# H11R0_Backend.net
KiCad netlist of a schematic drawn in Altium Designer
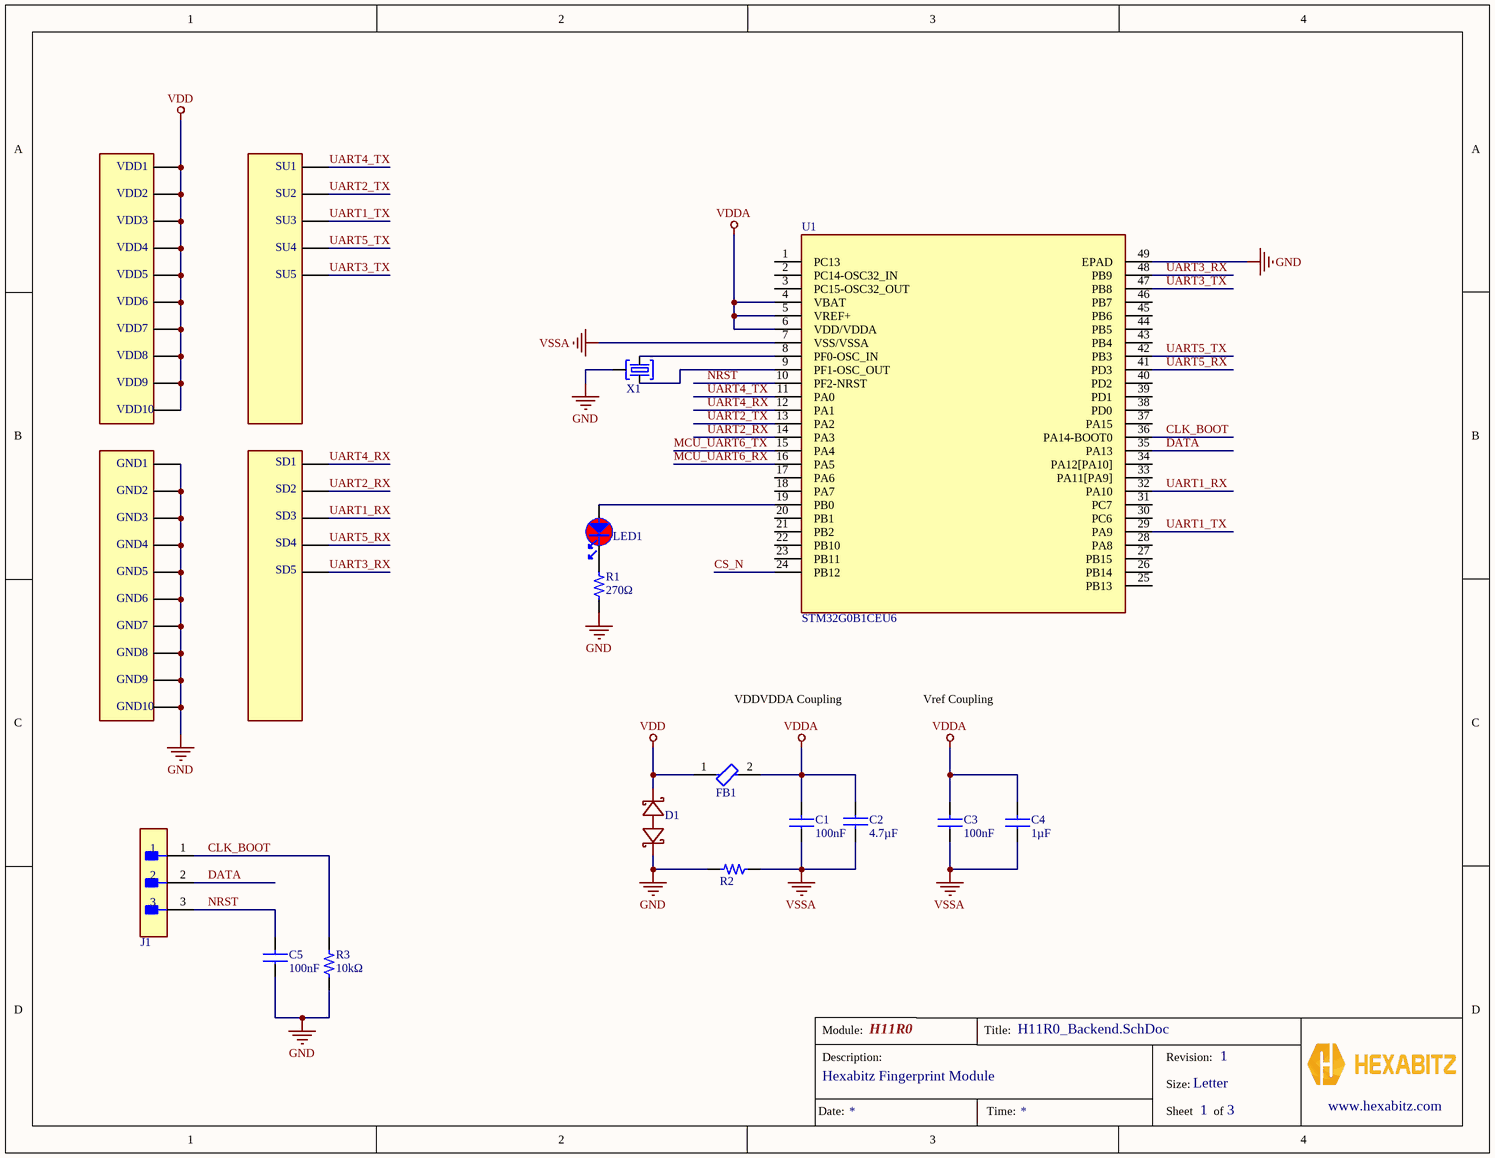
[diagram p0: H11R0_Backend.SchDoc]

(export (version "E")
  (design (tool "Eeschema 10.0.6"))
  (components
    (comp (ref "C1")
      (value "100nF")
      (footprint "C0603")
      (fields
        (field (name "MANUFACTURER") "Samsung Electro-Mechanics")
        (field (name "MANUFACTURER PART NUMBER") "CL10B104KA8NNNC")
        (field (name "TOLERANCE") "10%")
      )
      (libsource (lib "Hexabitz Altium Library") (part "generic Capacitor"))
    )
    (comp (ref "C2")
      (value "4.7µF")
      (footprint "C0805")
      (fields
        (field (name "MANUFACTURER") "Samsung Electro-Mechanics")
        (field (name "MANUFACTURER PART NUMBER") "CL21X475KAQNNNE")
        (field (name "TOLERANCE") "10%")
      )
      (libsource (lib "Hexabitz Altium Library") (part "generic Capacitor"))
    )
    (comp (ref "C3")
      (value "100nF")
      (footprint "C0603")
      (fields
        (field (name "MANUFACTURER") "Samsung Electro-Mechanics")
        (field (name "MANUFACTURER PART NUMBER") "CL10B104KA8NNNC")
        (field (name "TOLERANCE") "10%")
      )
      (libsource (lib "Hexabitz Altium Library") (part "generic Capacitor"))
    )
    (comp (ref "C4")
      (value "1µF")
      (footprint "C0805")
      (description "Ceramic Capacitor, Ceramic, 16V, 10% +Tol, 10% -Tol, X7R, 15% TC, 1uF, Surface Mount, 0805")
      (fields
        (field (name "MANUFACTURER") "Yageo Group")
        (field (name "MANUFACTURER PART NUMBER") "CC0805KKX7R7BB105")
      )
      (libsource (lib "Hexabitz Altium Library") (part "generic Capacitor"))
    )
    (comp (ref "C5")
      (value "100nF")
      (footprint "C0603")
      (fields
        (field (name "MANUFACTURER") "Samsung Electro-Mechanics")
        (field (name "MANUFACTURER PART NUMBER") "CL10B104KA8NNNC")
        (field (name "TOLERANCE") "10%")
      )
      (libsource (lib "Hexabitz Altium Library") (part "generic Capacitor"))
    )
    (comp (ref "D1")
      (value "CDSOD323-T03SC")
      (footprint "SOD2513X114N")
      (description "A 3V, 350W, bi-directional, standard capacitance, SOD323 pkg TVS Diode ¦ Bourns CDSOD323-T03SC")
      (fields (field (name "MANUFACTURER") "Bourns"))
      (libsource (lib "Hexabitz Altium Library") (part "CDSOD323-T03SC"))
    )
    (comp (ref "FB1")
      (value "MMZ1608Y300B")
      (footprint "FP-MMZ1608-0_8-MFG")
      (description "Ferrite Beads 0603 30ohms 1500mA Signal Line AEC-Q200")
      (fields
        (field (name "MANUFACTURER") "TDK")
        (field (name "MANUFACTURER PART NUMBER") "MMZ1608Y300BTD25")
      )
      (libsource (lib "Hexabitz Altium Library") (part "MMZ1608Y300B"))
    )
    (comp (ref "GND1")
      (value "HEXABIT_UART_PORT")
      (footprint "HEXABIT_POWER_PORT_D")
      (libsource (lib "hexabitz_connectors.Library") (part "HEXABIT_POWER_PORT_D"))
    )
    (comp (ref "GND2")
      (value "HEXABIT_UART_PORT")
      (footprint "HEXABIT_POWER_PORT_D")
      (libsource (lib "hexabitz_connectors.Library") (part "HEXABIT_POWER_PORT_D"))
    )
    (comp (ref "GND3")
      (value "HEXABIT_UART_PORT")
      (footprint "HEXABIT_POWER_PORT_D_300R")
      (libsource (lib "hexabitz_connectors.Library") (part "HEXABIT_POWER_PORT_D_300R"))
    )
    (comp (ref "GND4")
      (value "HEXABIT_UART_PORT")
      (footprint "HEXABIT_POWER_PORT_D")
      (libsource (lib "hexabitz_connectors.Library") (part "HEXABIT_POWER_PORT_D"))
    )
    (comp (ref "GND5")
      (value "HEXABIT_UART_PORT")
      (footprint "HEXABIT_POWER_PORT_D")
      (libsource (lib "hexabitz_connectors.Library") (part "HEXABIT_POWER_PORT_D"))
    )
    (comp (ref "GND6")
      (value "HEXABIT_UART_PORT")
      (footprint "HEXABIT_POWER_PORT_D")
      (libsource (lib "hexabitz_connectors.Library") (part "HEXABIT_POWER_PORT_D"))
    )
    (comp (ref "GND7")
      (value "HEXABIT_UART_PORT")
      (footprint "HEXABIT_POWER_PORT_D")
      (libsource (lib "hexabitz_connectors.Library") (part "HEXABIT_POWER_PORT_D"))
    )
    (comp (ref "GND8")
      (value "HEXABIT_UART_PORT")
      (footprint "HEXABIT_POWER_PORT_D_300L")
      (libsource (lib "hexabitz_connectors.Library") (part "HEXABIT_POWER_PORT_D_300L"))
    )
    (comp (ref "GND9")
      (value "HEXABIT_UART_PORT")
      (footprint "HEXABIT_POWER_PORT_D")
      (libsource (lib "hexabitz_connectors.Library") (part "HEXABIT_POWER_PORT_D"))
    )
    (comp (ref "GND10")
      (value "HEXABIT_UART_PORT")
      (footprint "HEXABIT_POWER_PORT_D")
      (libsource (lib "hexabitz_connectors.Library") (part "HEXABIT_POWER_PORT_D"))
    )
    (comp (ref "J1")
      (value "TSW-103-14-G-S")
      (footprint "FP-TSW-103-14-G-S-MFG")
      (description "CONN HEADER VERT 3POS 2.54MM")
      (libsource (lib "Altium Content Vault") (part "cd3439d6ef35ae5d9b27ec4fdd3e828"))
    )
    (comp (ref "LED1")
      (value "VLMS1300-GS08")
      (footprint "FP-6_541-5092_01-4-MFG")
      (description "LED Uni-Color Super Red 639nm 2-Pin Chip 0603(1608Metric) T/R")
      (fields (field (name "MANUFACTURER") "Vishay Semiconductors"))
      (libsource (lib "Hexabitz Altium Library") (part "VLMS1300-GS08"))
    )
    (comp (ref "R1")
      (value "270Ω")
      (footprint "R0603")
      (description "Res Thick Film 0603 270 Ohm 5% 0.1W(1/10W) ±200ppm/C Pad SMD Automotive T/R")
      (fields
        (field (name "MANUFACTURER") "Panasonic")
        (field (name "MANUFACTURER PART NUMBER") "ERJ-3GEYJ271V")
      )
      (libsource (lib "") (part "generic Resistor_2"))
    )
    (comp (ref "R2")
      (value "Manufacturer Part Number")
      (footprint "R0603")
      (libsource (lib "Hexabitz Altium Library") (part "generic Resistor"))
    )
    (comp (ref "R3")
      (value "10kΩ")
      (footprint "R0603")
      (description "100mW Thick Film Resistors ±100ppm/℃ ±1% 10kΩ 0603 Chip Resistor - Surface Mount ROHS")
      (fields
        (field (name "MANUFACTURER") "Yageo Group")
        (field (name "MANUFACTURER PART NUMBER") "RC0603FR-0710KL")
      )
      (libsource (lib "") (part "generic Resistor_1"))
    )
    (comp (ref "SD1")
      (value "HEXABIT_UART_PORT")
      (footprint "HEXABIT_UART_PORT_D")
      (libsource (lib "hexabitz_connectors.Library") (part "HEXABIT_UART_PORT_D"))
    )
    (comp (ref "SD2")
      (value "HEXABIT_UART_PORT")
      (footprint "HEXABIT_UART_PORT_D")
      (libsource (lib "hexabitz_connectors.Library") (part "HEXABIT_UART_PORT_D"))
    )
    (comp (ref "SD3")
      (value "HEXABIT_UART_PORT")
      (footprint "HEXABIT_UART_PORT_D")
      (libsource (lib "hexabitz_connectors.Library") (part "HEXABIT_UART_PORT_D"))
    )
    (comp (ref "SD4")
      (value "HEXABIT_UART_PORT")
      (footprint "HEXABIT_UART_PORT_D")
      (libsource (lib "hexabitz_connectors.Library") (part "HEXABIT_UART_PORT_D"))
    )
    (comp (ref "SD5")
      (value "HEXABIT_UART_PORT")
      (footprint "HEXABIT_UART_PORT_D")
      (libsource (lib "hexabitz_connectors.Library") (part "HEXABIT_UART_PORT_D"))
    )
    (comp (ref "SU1")
      (value "HEXABIT_UART_PORT")
      (footprint "HEXABIT_UART_PORT_U")
      (libsource (lib "hexabitz_connectors.Library") (part "HEXABIT_UART_PORT_U"))
    )
    (comp (ref "SU2")
      (value "HEXABIT_UART_PORT")
      (footprint "HEXABIT_UART_PORT_U")
      (libsource (lib "hexabitz_connectors.Library") (part "HEXABIT_UART_PORT_U"))
    )
    (comp (ref "SU3")
      (value "HEXABIT_UART_PORT")
      (footprint "HEXABIT_UART_PORT_U")
      (libsource (lib "hexabitz_connectors.Library") (part "HEXABIT_UART_PORT_U"))
    )
    (comp (ref "SU4")
      (value "HEXABIT_UART_PORT")
      (footprint "HEXABIT_UART_PORT_U")
      (libsource (lib "hexabitz_connectors.Library") (part "HEXABIT_UART_PORT_U"))
    )
    (comp (ref "SU5")
      (value "HEXABIT_UART_PORT")
      (footprint "HEXABIT_UART_PORT_U")
      (libsource (lib "hexabitz_connectors.Library") (part "HEXABIT_UART_PORT_U"))
    )
    (comp (ref "U1")
      (value "STM32G0B1CEU6")
      (footprint "QFN50P700X700X65-49N-D")
      (description "MCU 32-bit ARM Cortex M0+ RISC 512KB Flash 1.8V/2.5V/3.3V 48-Pin UFQFPN EP Tray")
      (fields
        (field (name "MANUFACTURER") "STMicroelectronics")
        (field (name "MANUFACTURER PART NUMBER") "STM32G0B1CEU6")
      )
      (libsource (lib "Hexabitz Altium Library") (part "STM32G0B1CEU6"))
    )
    (comp (ref "VDD1")
      (value "HEXABIT_UART_PORT")
      (footprint "HEXABIT_POWER_PORT_U")
      (libsource (lib "hexabitz_connectors.Library") (part "HEXABIT_POWER_PORT_U"))
    )
    (comp (ref "VDD2")
      (value "HEXABIT_UART_PORT")
      (footprint "HEXABIT_POWER_PORT_U")
      (libsource (lib "hexabitz_connectors.Library") (part "HEXABIT_POWER_PORT_U"))
    )
    (comp (ref "VDD3")
      (value "HEXABIT_UART_PORT")
      (footprint "HEXABIT_POWER_PORT_U_300R")
      (libsource (lib "hexabitz_connectors.Library") (part "HEXABIT_POWER_PORT_U_300R"))
    )
    (comp (ref "VDD4")
      (value "HEXABIT_UART_PORT")
      (footprint "HEXABIT_POWER_PORT_U")
      (libsource (lib "hexabitz_connectors.Library") (part "HEXABIT_POWER_PORT_U"))
    )
    (comp (ref "VDD5")
      (value "HEXABIT_UART_PORT")
      (footprint "HEXABIT_POWER_PORT_U")
      (libsource (lib "hexabitz_connectors.Library") (part "HEXABIT_POWER_PORT_U"))
    )
    (comp (ref "VDD6")
      (value "HEXABIT_UART_PORT")
      (footprint "HEXABIT_POWER_PORT_U")
      (libsource (lib "hexabitz_connectors.Library") (part "HEXABIT_POWER_PORT_U"))
    )
    (comp (ref "VDD7")
      (value "HEXABIT_UART_PORT")
      (footprint "HEXABIT_POWER_PORT_U")
      (libsource (lib "hexabitz_connectors.Library") (part "HEXABIT_POWER_PORT_U"))
    )
    (comp (ref "VDD8")
      (value "HEXABIT_UART_PORT")
      (footprint "HEXABIT_POWER_PORT_U_300L")
      (libsource (lib "hexabitz_connectors.Library") (part "HEXABIT_POWER_PORT_U_300L"))
    )
    (comp (ref "VDD9")
      (value "HEXABIT_UART_PORT")
      (footprint "HEXABIT_POWER_PORT_U")
      (libsource (lib "hexabitz_connectors.Library") (part "HEXABIT_POWER_PORT_U"))
    )
    (comp (ref "VDD10")
      (value "HEXABIT_UART_PORT")
      (footprint "HEXABIT_POWER_PORT_U")
      (libsource (lib "hexabitz_connectors.Library") (part "HEXABIT_POWER_PORT_U"))
    )
    (comp (ref "X1")
      (value "CSTCE8M00G52Z-R0")
      (footprint "XTALL_CSTCE8M00G52")
      (description "Ceramic Resonator 8MHz ±0.5% (Tol) ±0.2% (Stability) 10pF 40Ohm 3-Pin CSMD T/R")
      (fields (field (name "MANUFACTURER") "Murata") (field (name "TOLERANCE") "0.5%"))
      (libsource (lib "Hexabitz Altium Library") (part "CSTCE8M00G52Z-R0"))
    )
  )
  (nets
    (net (code "1") (name "/CLK_BOOT") (class "Default")
      (node (ref "J1") (pin "1") (pinfunction "1_1") (pintype "passive"))
      (node (ref "R3") (pin "1") (pinfunction "1_1") (pintype "passive"))
      (node (ref "U1") (pin "36") (pinfunction "PA14-BOOT0_36") (pintype "passive"))
    )
    (net (code "2") (name "/CS_N") (class "Default")
      (node (ref "U1") (pin "24") (pinfunction "PB12_24") (pintype "passive"))
    )
    (net (code "3") (name "/DATA") (class "Default")
      (node (ref "J1") (pin "2") (pinfunction "2_2") (pintype "passive"))
      (node (ref "U1") (pin "35") (pinfunction "PA13_35") (pintype "passive"))
    )
    (net (code "4") (name "/MCU_UART6_RX") (class "Default")
      (node (ref "U1") (pin "16") (pinfunction "PA5_16") (pintype "passive"))
    )
    (net (code "5") (name "/MCU_UART6_TX") (class "Default")
      (node (ref "U1") (pin "15") (pinfunction "PA4_15") (pintype "passive"))
    )
    (net (code "6") (name "/NRST") (class "Default")
      (node (ref "C5") (pin "2") (pinfunction "2_2") (pintype "passive"))
      (node (ref "J1") (pin "3") (pinfunction "3_3") (pintype "passive"))
      (node (ref "U1") (pin "10") (pinfunction "PF2-NRST_10") (pintype "passive"))
    )
    (net (code "7") (name "/UART1_RX") (class "Default")
      (node (ref "SD3") (pin "UART_D") (pinfunction "UART_D_UART_D") (pintype "passive"))
      (node (ref "U1") (pin "32") (pinfunction "PA10_32") (pintype "passive"))
    )
    (net (code "8") (name "/UART1_TX") (class "Default")
      (node (ref "SU3") (pin "UART_U") (pinfunction "UART_U_UART_U") (pintype "passive"))
      (node (ref "U1") (pin "29") (pinfunction "PA9_29") (pintype "passive"))
    )
    (net (code "9") (name "/UART2_RX") (class "Default")
      (node (ref "SD2") (pin "UART_D") (pinfunction "UART_D_UART_D") (pintype "passive"))
      (node (ref "U1") (pin "14") (pinfunction "PA3_14") (pintype "passive"))
    )
    (net (code "10") (name "/UART2_TX") (class "Default")
      (node (ref "SU2") (pin "UART_U") (pinfunction "UART_U_UART_U") (pintype "passive"))
      (node (ref "U1") (pin "13") (pinfunction "PA2_13") (pintype "passive"))
    )
    (net (code "11") (name "/UART3_RX") (class "Default")
      (node (ref "SD5") (pin "UART_D") (pinfunction "UART_D_UART_D") (pintype "passive"))
      (node (ref "U1") (pin "48") (pinfunction "PB9_48") (pintype "passive"))
    )
    (net (code "12") (name "/UART3_TX") (class "Default")
      (node (ref "SU5") (pin "UART_U") (pinfunction "UART_U_UART_U") (pintype "passive"))
      (node (ref "U1") (pin "47") (pinfunction "PB8_47") (pintype "passive"))
    )
    (net (code "13") (name "/UART4_RX") (class "Default")
      (node (ref "SD1") (pin "UART_D") (pinfunction "UART_D_UART_D") (pintype "passive"))
      (node (ref "U1") (pin "12") (pinfunction "PA1_12") (pintype "passive"))
    )
    (net (code "14") (name "/UART4_TX") (class "Default")
      (node (ref "SU1") (pin "UART_U") (pinfunction "UART_U_UART_U") (pintype "passive"))
      (node (ref "U1") (pin "11") (pinfunction "PA0_11") (pintype "passive"))
    )
    (net (code "15") (name "/UART5_RX") (class "Default")
      (node (ref "SD4") (pin "UART_D") (pinfunction "UART_D_UART_D") (pintype "passive"))
      (node (ref "U1") (pin "41") (pinfunction "PD3_41") (pintype "passive"))
    )
    (net (code "16") (name "/UART5_TX") (class "Default")
      (node (ref "SU4") (pin "UART_U") (pinfunction "UART_U_UART_U") (pintype "passive"))
      (node (ref "U1") (pin "42") (pinfunction "PB3_42") (pintype "passive"))
    )
    (net (code "17") (name "GND") (class "Default")
      (node (ref "C5") (pin "1") (pinfunction "1_1") (pintype "passive"))
      (node (ref "D1") (pin "1") (pinfunction "A_1") (pintype "passive"))
      (node (ref "GND1") (pin "Pwr_D") (pinfunction "Pwr_D_Pwr_D") (pintype "passive"))
      (node (ref "GND10") (pin "Pwr_D") (pinfunction "Pwr_D_Pwr_D") (pintype "passive"))
      (node (ref "GND2") (pin "Pwr_D") (pinfunction "Pwr_D_Pwr_D") (pintype "passive"))
      (node (ref "GND3") (pin "Pwr_D") (pinfunction "Pwr_D_Pwr_D") (pintype "passive"))
      (node (ref "GND4") (pin "Pwr_D") (pinfunction "Pwr_D_Pwr_D") (pintype "passive"))
      (node (ref "GND5") (pin "Pwr_D") (pinfunction "Pwr_D_Pwr_D") (pintype "passive"))
      (node (ref "GND6") (pin "Pwr_D") (pinfunction "Pwr_D_Pwr_D") (pintype "passive"))
      (node (ref "GND7") (pin "Pwr_D") (pinfunction "Pwr_D_Pwr_D") (pintype "passive"))
      (node (ref "GND8") (pin "Pwr_D") (pinfunction "Pwr_D_Pwr_D") (pintype "passive"))
      (node (ref "GND9") (pin "Pwr_D") (pinfunction "Pwr_D_Pwr_D") (pintype "passive"))
      (node (ref "R1") (pin "1") (pinfunction "1_1") (pintype "passive"))
      (node (ref "R2") (pin "1") (pinfunction "1_1") (pintype "passive"))
      (node (ref "R3") (pin "2") (pinfunction "2_2") (pintype "passive"))
      (node (ref "U1") (pin "49") (pinfunction "EPAD_49") (pintype "passive"))
      (node (ref "X1") (pin "P$2") (pinfunction "2_P$2") (pintype "passive"))
    )
    (net (code "18") (name "Net-(LED1-Pad1)") (class "Default")
      (node (ref "LED1") (pin "1") (pintype "passive"))
      (node (ref "R1") (pin "2") (pinfunction "2_2") (pintype "passive"))
    )
    (net (code "19") (name "Net-(U1-PB0)") (class "Default")
      (node (ref "LED1") (pin "2") (pintype "passive"))
      (node (ref "U1") (pin "19") (pinfunction "PB0_19") (pintype "passive"))
    )
    (net (code "20") (name "Net-(U1-PF0-OSC_IN)") (class "Default")
      (node (ref "U1") (pin "8") (pinfunction "PF0-OSC_IN_8") (pintype "passive"))
      (node (ref "X1") (pin "P$3") (pinfunction "3_P$3") (pintype "passive"))
    )
    (net (code "21") (name "Net-(U1-PF1-OSC_OUT)") (class "Default")
      (node (ref "U1") (pin "9") (pinfunction "PF1-OSC_OUT_9") (pintype "passive"))
      (node (ref "X1") (pin "P$1") (pinfunction "1_P$1") (pintype "passive"))
    )
    (net (code "22") (name "VDD") (class "Default")
      (node (ref "D1") (pin "2") (pinfunction "C_2") (pintype "passive"))
      (node (ref "FB1") (pin "1") (pinfunction "1_1") (pintype "passive"))
      (node (ref "VDD1") (pin "Pwr_U") (pinfunction "Pwr_U_Pwr_U") (pintype "passive"))
      (node (ref "VDD10") (pin "Pwr_U") (pinfunction "Pwr_U_Pwr_U") (pintype "passive"))
      (node (ref "VDD2") (pin "Pwr_U") (pinfunction "Pwr_U_Pwr_U") (pintype "passive"))
      (node (ref "VDD3") (pin "Pwr_U") (pinfunction "Pwr_U_Pwr_U") (pintype "passive"))
      (node (ref "VDD4") (pin "Pwr_U") (pinfunction "Pwr_U_Pwr_U") (pintype "passive"))
      (node (ref "VDD5") (pin "Pwr_U") (pinfunction "Pwr_U_Pwr_U") (pintype "passive"))
      (node (ref "VDD6") (pin "Pwr_U") (pinfunction "Pwr_U_Pwr_U") (pintype "passive"))
      (node (ref "VDD7") (pin "Pwr_U") (pinfunction "Pwr_U_Pwr_U") (pintype "passive"))
      (node (ref "VDD8") (pin "Pwr_U") (pinfunction "Pwr_U_Pwr_U") (pintype "passive"))
      (node (ref "VDD9") (pin "Pwr_U") (pinfunction "Pwr_U_Pwr_U") (pintype "passive"))
    )
    (net (code "23") (name "VDDA") (class "Default")
      (node (ref "C1") (pin "2") (pinfunction "2_2") (pintype "passive"))
      (node (ref "C2") (pin "1") (pinfunction "1_1") (pintype "passive"))
      (node (ref "C3") (pin "2") (pinfunction "2_2") (pintype "passive"))
      (node (ref "C4") (pin "2") (pinfunction "2_2") (pintype "passive"))
      (node (ref "FB1") (pin "2") (pinfunction "2_2") (pintype "passive"))
      (node (ref "U1") (pin "4") (pinfunction "VBAT_4") (pintype "passive"))
      (node (ref "U1") (pin "5") (pinfunction "VREF+_5") (pintype "passive"))
      (node (ref "U1") (pin "6") (pinfunction "VDD/VDDA_6") (pintype "passive"))
    )
    (net (code "24") (name "VSSA") (class "Default")
      (node (ref "C1") (pin "1") (pinfunction "1_1") (pintype "passive"))
      (node (ref "C2") (pin "2") (pinfunction "2_2") (pintype "passive"))
      (node (ref "C3") (pin "1") (pinfunction "1_1") (pintype "passive"))
      (node (ref "C4") (pin "1") (pinfunction "1_1") (pintype "passive"))
      (node (ref "R2") (pin "2") (pinfunction "2_2") (pintype "passive"))
      (node (ref "U1") (pin "7") (pinfunction "VSS/VSSA_7") (pintype "passive"))
    )
    (net (code "25") (name "unconnected-(U1-PA6-Pad17)") (class "Default")
      (node (ref "U1") (pin "17") (pinfunction "PA6_17") (pintype "passive"))
    )
    (net (code "26") (name "unconnected-(U1-PA7-Pad18)") (class "Default")
      (node (ref "U1") (pin "18") (pinfunction "PA7_18") (pintype "passive"))
    )
    (net (code "27") (name "unconnected-(U1-PA8-Pad28)") (class "Default")
      (node (ref "U1") (pin "28") (pinfunction "PA8_28") (pintype "passive"))
    )
    (net (code "28") (name "unconnected-(U1-PA11[PA9]-Pad33)") (class "Default")
      (node (ref "U1") (pin "33") (pinfunction "PA11[PA9]_33") (pintype "passive"))
    )
    (net (code "29") (name "unconnected-(U1-PA12[PA10]-Pad34)") (class "Default")
      (node (ref "U1") (pin "34") (pinfunction "PA12[PA10]_34") (pintype "passive"))
    )
    (net (code "30") (name "unconnected-(U1-PA15-Pad37)") (class "Default")
      (node (ref "U1") (pin "37") (pinfunction "PA15_37") (pintype "passive"))
    )
    (net (code "31") (name "unconnected-(U1-PB1-Pad20)") (class "Default")
      (node (ref "U1") (pin "20") (pinfunction "PB1_20") (pintype "passive"))
    )
    (net (code "32") (name "unconnected-(U1-PB2-Pad21)") (class "Default")
      (node (ref "U1") (pin "21") (pinfunction "PB2_21") (pintype "passive"))
    )
    (net (code "33") (name "unconnected-(U1-PB4-Pad43)") (class "Default")
      (node (ref "U1") (pin "43") (pinfunction "PB4_43") (pintype "passive"))
    )
    (net (code "34") (name "unconnected-(U1-PB5-Pad44)") (class "Default")
      (node (ref "U1") (pin "44") (pinfunction "PB5_44") (pintype "passive"))
    )
    (net (code "35") (name "unconnected-(U1-PB6-Pad45)") (class "Default")
      (node (ref "U1") (pin "45") (pinfunction "PB6_45") (pintype "passive"))
    )
    (net (code "36") (name "unconnected-(U1-PB7-Pad46)") (class "Default")
      (node (ref "U1") (pin "46") (pinfunction "PB7_46") (pintype "passive"))
    )
    (net (code "37") (name "unconnected-(U1-PB10-Pad22)") (class "Default")
      (node (ref "U1") (pin "22") (pinfunction "PB10_22") (pintype "passive"))
    )
    (net (code "38") (name "unconnected-(U1-PB11-Pad23)") (class "Default")
      (node (ref "U1") (pin "23") (pinfunction "PB11_23") (pintype "passive"))
    )
    (net (code "39") (name "unconnected-(U1-PB13-Pad25)") (class "Default")
      (node (ref "U1") (pin "25") (pinfunction "PB13_25") (pintype "passive"))
    )
    (net (code "40") (name "unconnected-(U1-PB14-Pad26)") (class "Default")
      (node (ref "U1") (pin "26") (pinfunction "PB14_26") (pintype "passive"))
    )
    (net (code "41") (name "unconnected-(U1-PB15-Pad27)") (class "Default")
      (node (ref "U1") (pin "27") (pinfunction "PB15_27") (pintype "passive"))
    )
    (net (code "42") (name "unconnected-(U1-PC6-Pad30)") (class "Default")
      (node (ref "U1") (pin "30") (pinfunction "PC6_30") (pintype "passive"))
    )
    (net (code "43") (name "unconnected-(U1-PC7-Pad31)") (class "Default")
      (node (ref "U1") (pin "31") (pinfunction "PC7_31") (pintype "passive"))
    )
    (net (code "44") (name "unconnected-(U1-PC13-Pad1)") (class "Default")
      (node (ref "U1") (pin "1") (pinfunction "PC13_1") (pintype "passive"))
    )
    (net (code "45") (name "unconnected-(U1-PC14-OSC32_IN-Pad2)") (class "Default")
      (node (ref "U1") (pin "2") (pinfunction "PC14-OSC32_IN_2") (pintype "passive"))
    )
    (net (code "46") (name "unconnected-(U1-PC15-OSC32_OUT-Pad3)") (class "Default")
      (node (ref "U1") (pin "3") (pinfunction "PC15-OSC32_OUT_3") (pintype "passive"))
    )
    (net (code "47") (name "unconnected-(U1-PD0-Pad38)") (class "Default")
      (node (ref "U1") (pin "38") (pinfunction "PD0_38") (pintype "passive"))
    )
    (net (code "48") (name "unconnected-(U1-PD1-Pad39)") (class "Default")
      (node (ref "U1") (pin "39") (pinfunction "PD1_39") (pintype "passive"))
    )
    (net (code "49") (name "unconnected-(U1-PD2-Pad40)") (class "Default")
      (node (ref "U1") (pin "40") (pinfunction "PD2_40") (pintype "passive"))
    )
  )
)
